# DRS4_GPIO_EXPANDER.net
KiCad netlist of a schematic drawn in Altium Designer
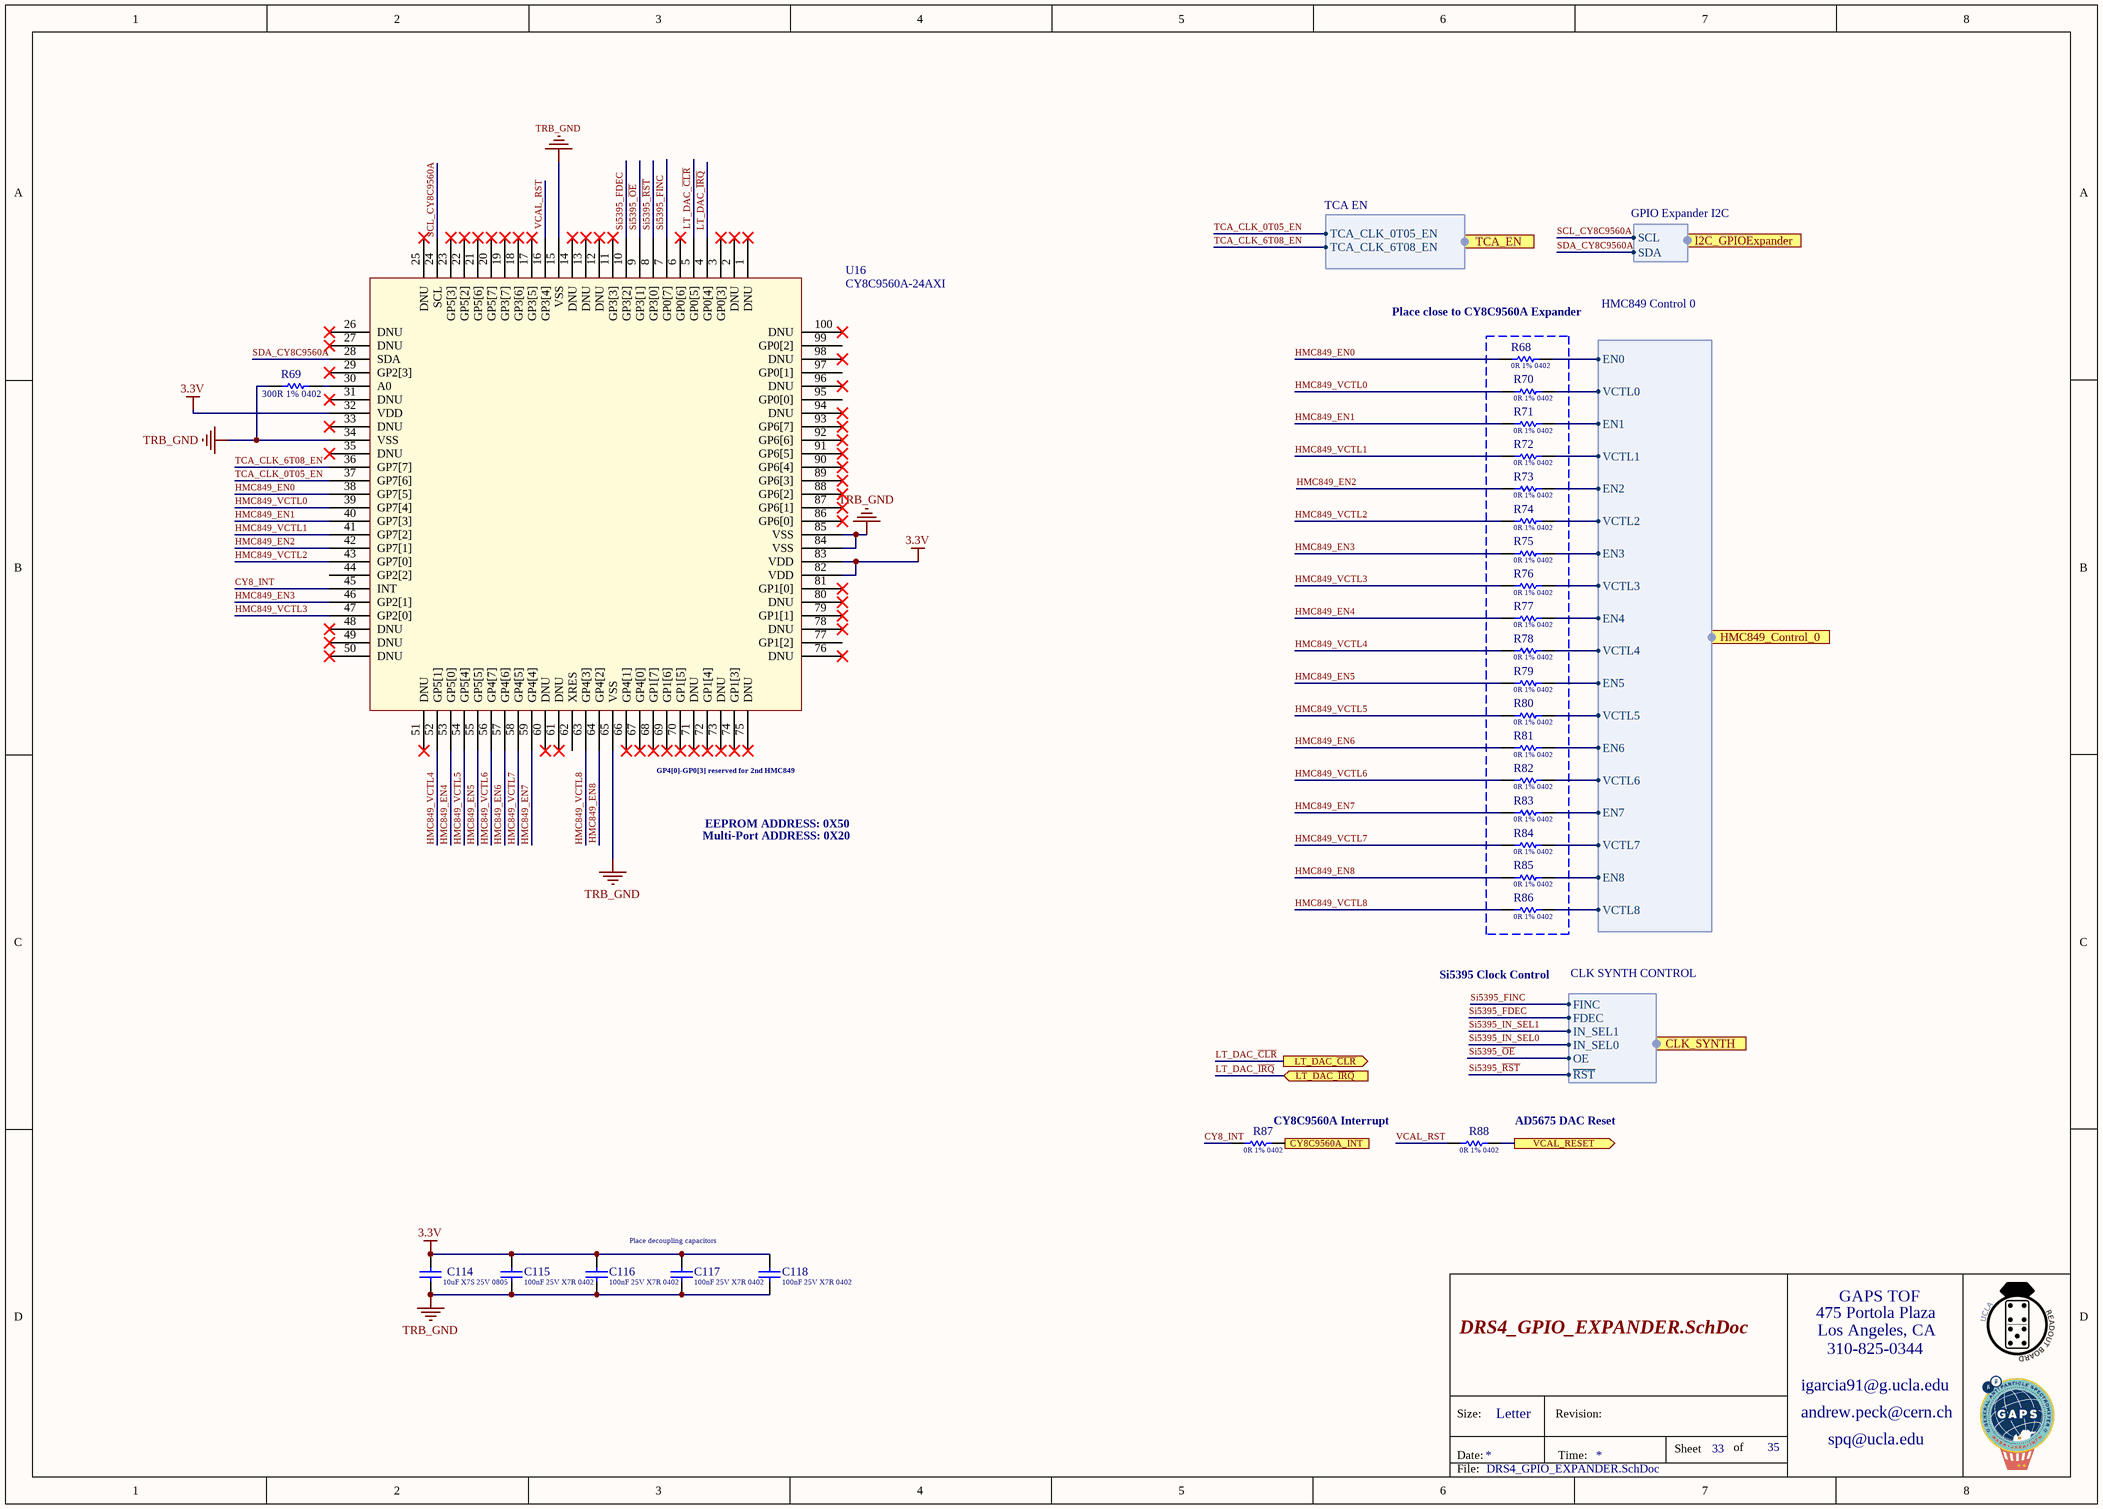
[diagram p0: DRS4_GPIO_EXPANDER.SchDoc]

(export (version "E")
  (design (tool "Eeschema 10.0.6"))
  (components
    (comp (ref "C114")
      (value "Cap_Murata_ GRM21BC71E106ME11L_10uF")
      (footprint "Cap_Murata_ GRM21BC71E106ME11L_10uF")
      (description "CAP CER 10uF 25V X7R 0805")
      (fields (field (name "CAPACITANCE") "10uF X7S 25V 0805"))
      (libsource (lib "Cap_Murata_ GRM21BC71E106ME11L_10uF") (part "Cap_Murata_ GRM21BC71E106ME11L_10uF"))
    )
    (comp (ref "C115")
      (value "Cap_Taiyo_Yuden_TMK105B7104KV-FR_100nF")
      (footprint "Cap_Taiyo_Yuden_TMK105B7104KV-FR_100nF")
      (description "CAP CER 100nF 25V X7R 0402")
      (fields (field (name "CAPACITANCE") "100nF 25V X7R 0402"))
      (libsource (lib "Cap_Taiyo_Yuden_TMK105B7104KV-FR_100nF") (part "Cap_Taiyo_Yuden_TMK105B7104KV-FR_100nF"))
    )
    (comp (ref "C116")
      (value "Cap_Taiyo_Yuden_TMK105B7104KV-FR_100nF")
      (footprint "Cap_Taiyo_Yuden_TMK105B7104KV-FR_100nF")
      (description "CAP CER 100nF 25V X7R 0402")
      (fields (field (name "CAPACITANCE") "100nF 25V X7R 0402"))
      (libsource (lib "Cap_Taiyo_Yuden_TMK105B7104KV-FR_100nF") (part "Cap_Taiyo_Yuden_TMK105B7104KV-FR_100nF"))
    )
    (comp (ref "C117")
      (value "Cap_Taiyo_Yuden_TMK105B7104KV-FR_100nF")
      (footprint "Cap_Taiyo_Yuden_TMK105B7104KV-FR_100nF")
      (description "CAP CER 100nF 25V X7R 0402")
      (fields (field (name "CAPACITANCE") "100nF 25V X7R 0402"))
      (libsource (lib "Cap_Taiyo_Yuden_TMK105B7104KV-FR_100nF") (part "Cap_Taiyo_Yuden_TMK105B7104KV-FR_100nF"))
    )
    (comp (ref "C118")
      (value "Cap_Taiyo_Yuden_TMK105B7104KV-FR_100nF")
      (footprint "Cap_Taiyo_Yuden_TMK105B7104KV-FR_100nF")
      (description "CAP CER 100nF 25V X7R 0402")
      (fields (field (name "CAPACITANCE") "100nF 25V X7R 0402"))
      (libsource (lib "Cap_Taiyo_Yuden_TMK105B7104KV-FR_100nF") (part "Cap_Taiyo_Yuden_TMK105B7104KV-FR_100nF"))
    )
    (comp (ref "R68")
      (value "Res_Vishay_CRCW04020000Z0EDC_0_Ohm")
      (footprint "Res_Vishay_CRCW04020000Z0EDC_0_Ohm")
      (description "0R 0.062W 1% 0402 (1005 Metric)  SMD")
      (fields (field (name "RESISTANCE") "0R 1% 0402"))
      (libsource (lib "Res_Vishay_CRCW04020000Z0EDC_0_Ohm") (part "Res_Vishay_CRCW04020000Z0EDC_0_Ohm"))
    )
    (comp (ref "R69")
      (value "300R 1% 0402")
      (footprint "RESC0402(1005)_L")
      (description "300R 0.063W 1% 0402 (1005 Metric)  SMD")
      (fields (field (name "TOLERANCE") "1 %") (field (name "POWER") "0.063 W"))
      (libsource (lib "Altium Content Vault") (part "RES"))
    )
    (comp (ref "R70")
      (value "Res_Vishay_CRCW04020000Z0EDC_0_Ohm")
      (footprint "Res_Vishay_CRCW04020000Z0EDC_0_Ohm")
      (description "0R 0.062W 1% 0402 (1005 Metric)  SMD")
      (fields (field (name "RESISTANCE") "0R 1% 0402"))
      (libsource (lib "Res_Vishay_CRCW04020000Z0EDC_0_Ohm") (part "Res_Vishay_CRCW04020000Z0EDC_0_Ohm"))
    )
    (comp (ref "R71")
      (value "Res_Vishay_CRCW04020000Z0EDC_0_Ohm")
      (footprint "Res_Vishay_CRCW04020000Z0EDC_0_Ohm")
      (description "0R 0.062W 1% 0402 (1005 Metric)  SMD")
      (fields (field (name "RESISTANCE") "0R 1% 0402"))
      (libsource (lib "Res_Vishay_CRCW04020000Z0EDC_0_Ohm") (part "Res_Vishay_CRCW04020000Z0EDC_0_Ohm"))
    )
    (comp (ref "R72")
      (value "Res_Vishay_CRCW04020000Z0EDC_0_Ohm")
      (footprint "Res_Vishay_CRCW04020000Z0EDC_0_Ohm")
      (description "0R 0.062W 1% 0402 (1005 Metric)  SMD")
      (fields (field (name "RESISTANCE") "0R 1% 0402"))
      (libsource (lib "Res_Vishay_CRCW04020000Z0EDC_0_Ohm") (part "Res_Vishay_CRCW04020000Z0EDC_0_Ohm"))
    )
    (comp (ref "R73")
      (value "Res_Vishay_CRCW04020000Z0EDC_0_Ohm")
      (footprint "Res_Vishay_CRCW04020000Z0EDC_0_Ohm")
      (description "0R 0.062W 1% 0402 (1005 Metric)  SMD")
      (fields (field (name "RESISTANCE") "0R 1% 0402"))
      (libsource (lib "Res_Vishay_CRCW04020000Z0EDC_0_Ohm") (part "Res_Vishay_CRCW04020000Z0EDC_0_Ohm"))
    )
    (comp (ref "R74")
      (value "Res_Vishay_CRCW04020000Z0EDC_0_Ohm")
      (footprint "Res_Vishay_CRCW04020000Z0EDC_0_Ohm")
      (description "0R 0.062W 1% 0402 (1005 Metric)  SMD")
      (fields (field (name "RESISTANCE") "0R 1% 0402"))
      (libsource (lib "Res_Vishay_CRCW04020000Z0EDC_0_Ohm") (part "Res_Vishay_CRCW04020000Z0EDC_0_Ohm"))
    )
    (comp (ref "R75")
      (value "Res_Vishay_CRCW04020000Z0EDC_0_Ohm")
      (footprint "Res_Vishay_CRCW04020000Z0EDC_0_Ohm")
      (description "0R 0.062W 1% 0402 (1005 Metric)  SMD")
      (fields (field (name "RESISTANCE") "0R 1% 0402"))
      (libsource (lib "Res_Vishay_CRCW04020000Z0EDC_0_Ohm") (part "Res_Vishay_CRCW04020000Z0EDC_0_Ohm"))
    )
    (comp (ref "R76")
      (value "Res_Vishay_CRCW04020000Z0EDC_0_Ohm")
      (footprint "Res_Vishay_CRCW04020000Z0EDC_0_Ohm")
      (description "0R 0.062W 1% 0402 (1005 Metric)  SMD")
      (fields (field (name "RESISTANCE") "0R 1% 0402"))
      (libsource (lib "Res_Vishay_CRCW04020000Z0EDC_0_Ohm") (part "Res_Vishay_CRCW04020000Z0EDC_0_Ohm"))
    )
    (comp (ref "R77")
      (value "Res_Vishay_CRCW04020000Z0EDC_0_Ohm")
      (footprint "Res_Vishay_CRCW04020000Z0EDC_0_Ohm")
      (description "0R 0.062W 1% 0402 (1005 Metric)  SMD")
      (fields (field (name "RESISTANCE") "0R 1% 0402"))
      (libsource (lib "Res_Vishay_CRCW04020000Z0EDC_0_Ohm") (part "Res_Vishay_CRCW04020000Z0EDC_0_Ohm"))
    )
    (comp (ref "R78")
      (value "Res_Vishay_CRCW04020000Z0EDC_0_Ohm")
      (footprint "Res_Vishay_CRCW04020000Z0EDC_0_Ohm")
      (description "0R 0.062W 1% 0402 (1005 Metric)  SMD")
      (fields (field (name "RESISTANCE") "0R 1% 0402"))
      (libsource (lib "Res_Vishay_CRCW04020000Z0EDC_0_Ohm") (part "Res_Vishay_CRCW04020000Z0EDC_0_Ohm"))
    )
    (comp (ref "R79")
      (value "Res_Vishay_CRCW04020000Z0EDC_0_Ohm")
      (footprint "Res_Vishay_CRCW04020000Z0EDC_0_Ohm")
      (description "0R 0.062W 1% 0402 (1005 Metric)  SMD")
      (fields (field (name "RESISTANCE") "0R 1% 0402"))
      (libsource (lib "Res_Vishay_CRCW04020000Z0EDC_0_Ohm") (part "Res_Vishay_CRCW04020000Z0EDC_0_Ohm"))
    )
    (comp (ref "R80")
      (value "Res_Vishay_CRCW04020000Z0EDC_0_Ohm")
      (footprint "Res_Vishay_CRCW04020000Z0EDC_0_Ohm")
      (description "0R 0.062W 1% 0402 (1005 Metric)  SMD")
      (fields (field (name "RESISTANCE") "0R 1% 0402"))
      (libsource (lib "Res_Vishay_CRCW04020000Z0EDC_0_Ohm") (part "Res_Vishay_CRCW04020000Z0EDC_0_Ohm"))
    )
    (comp (ref "R81")
      (value "Res_Vishay_CRCW04020000Z0EDC_0_Ohm")
      (footprint "Res_Vishay_CRCW04020000Z0EDC_0_Ohm")
      (description "0R 0.062W 1% 0402 (1005 Metric)  SMD")
      (fields (field (name "RESISTANCE") "0R 1% 0402"))
      (libsource (lib "Res_Vishay_CRCW04020000Z0EDC_0_Ohm") (part "Res_Vishay_CRCW04020000Z0EDC_0_Ohm"))
    )
    (comp (ref "R82")
      (value "Res_Vishay_CRCW04020000Z0EDC_0_Ohm")
      (footprint "Res_Vishay_CRCW04020000Z0EDC_0_Ohm")
      (description "0R 0.062W 1% 0402 (1005 Metric)  SMD")
      (fields (field (name "RESISTANCE") "0R 1% 0402"))
      (libsource (lib "Res_Vishay_CRCW04020000Z0EDC_0_Ohm") (part "Res_Vishay_CRCW04020000Z0EDC_0_Ohm"))
    )
    (comp (ref "R83")
      (value "Res_Vishay_CRCW04020000Z0EDC_0_Ohm")
      (footprint "Res_Vishay_CRCW04020000Z0EDC_0_Ohm")
      (description "0R 0.062W 1% 0402 (1005 Metric)  SMD")
      (fields (field (name "RESISTANCE") "0R 1% 0402"))
      (libsource (lib "Res_Vishay_CRCW04020000Z0EDC_0_Ohm") (part "Res_Vishay_CRCW04020000Z0EDC_0_Ohm"))
    )
    (comp (ref "R84")
      (value "Res_Vishay_CRCW04020000Z0EDC_0_Ohm")
      (footprint "Res_Vishay_CRCW04020000Z0EDC_0_Ohm")
      (description "0R 0.062W 1% 0402 (1005 Metric)  SMD")
      (fields (field (name "RESISTANCE") "0R 1% 0402"))
      (libsource (lib "Res_Vishay_CRCW04020000Z0EDC_0_Ohm") (part "Res_Vishay_CRCW04020000Z0EDC_0_Ohm"))
    )
    (comp (ref "R85")
      (value "Res_Vishay_CRCW04020000Z0EDC_0_Ohm")
      (footprint "Res_Vishay_CRCW04020000Z0EDC_0_Ohm")
      (description "0R 0.062W 1% 0402 (1005 Metric)  SMD")
      (fields (field (name "RESISTANCE") "0R 1% 0402"))
      (libsource (lib "Res_Vishay_CRCW04020000Z0EDC_0_Ohm") (part "Res_Vishay_CRCW04020000Z0EDC_0_Ohm"))
    )
    (comp (ref "R86")
      (value "Res_Vishay_CRCW04020000Z0EDC_0_Ohm")
      (footprint "Res_Vishay_CRCW04020000Z0EDC_0_Ohm")
      (description "0R 0.062W 1% 0402 (1005 Metric)  SMD")
      (fields (field (name "RESISTANCE") "0R 1% 0402"))
      (libsource (lib "Res_Vishay_CRCW04020000Z0EDC_0_Ohm") (part "Res_Vishay_CRCW04020000Z0EDC_0_Ohm"))
    )
    (comp (ref "R87")
      (value "Res_Vishay_CRCW04020000Z0EDC_0_Ohm")
      (footprint "Res_Vishay_CRCW04020000Z0EDC_0_Ohm")
      (description "0R 0.062W 1% 0402 (1005 Metric)  SMD")
      (fields (field (name "RESISTANCE") "0R 1% 0402"))
      (libsource (lib "Res_Vishay_CRCW04020000Z0EDC_0_Ohm") (part "Res_Vishay_CRCW04020000Z0EDC_0_Ohm"))
    )
    (comp (ref "R88")
      (value "Res_Vishay_CRCW04020000Z0EDC_0_Ohm")
      (footprint "Res_Vishay_CRCW04020000Z0EDC_0_Ohm")
      (description "0R 0.062W 1% 0402 (1005 Metric)  SMD")
      (fields (field (name "RESISTANCE") "0R 1% 0402"))
      (libsource (lib "Res_Vishay_CRCW04020000Z0EDC_0_Ohm") (part "Res_Vishay_CRCW04020000Z0EDC_0_Ohm"))
    )
    (comp (ref "U16")
      (value "IC_Cypress_Semiconductor_CY8C9560A-24AXI")
      (footprint "IC_Cypress_Semiconductor_CY8C9560A-24AXI")
      (description "Interface - I/O Expanders 60BIT IO EXPANDER W/EEPROM")
      (fields (field (name "SERIES") "CY8C9560A-24AXI"))
      (libsource (lib "IC_Cypress_Semiconductor_CY8C9560A-24AXI") (part "IC_Cypress_Semiconductor_CY8C9560A-24AXI"))
    )
  )
  (nets
    (net (code "12") (name "/CY8C9560A_INT") (class "Default")
      (node (ref "R87") (pin "1") (pinfunction "1_1") (pintype "passive"))
    )
    (net (code "13") (name "/CY8_INT") (class "Default")
      (node (ref "R87") (pin "2") (pinfunction "2_2") (pintype "passive"))
      (node (ref "U16") (pin "45") (pinfunction "INT_45") (pintype "passive"))
    )
    (net (code "14") (name "/EN0") (class "Default")
      (node (ref "R68") (pin "2") (pinfunction "2_2") (pintype "passive"))
    )
    (net (code "15") (name "/EN1") (class "Default")
      (node (ref "R71") (pin "2") (pinfunction "2_2") (pintype "passive"))
    )
    (net (code "16") (name "/EN2") (class "Default")
      (node (ref "R73") (pin "2") (pinfunction "2_2") (pintype "passive"))
    )
    (net (code "17") (name "/EN3") (class "Default")
      (node (ref "R75") (pin "2") (pinfunction "2_2") (pintype "passive"))
    )
    (net (code "18") (name "/EN4") (class "Default")
      (node (ref "R77") (pin "2") (pinfunction "2_2") (pintype "passive"))
    )
    (net (code "19") (name "/EN5") (class "Default")
      (node (ref "R79") (pin "2") (pinfunction "2_2") (pintype "passive"))
    )
    (net (code "20") (name "/EN6") (class "Default")
      (node (ref "R81") (pin "2") (pinfunction "2_2") (pintype "passive"))
    )
    (net (code "21") (name "/EN7") (class "Default")
      (node (ref "R83") (pin "2") (pinfunction "2_2") (pintype "passive"))
    )
    (net (code "22") (name "/EN8") (class "Default")
      (node (ref "R85") (pin "2") (pinfunction "2_2") (pintype "passive"))
    )
    (net (code "23") (name "/HMC849_EN0") (class "Default")
      (node (ref "R68") (pin "1") (pinfunction "1_1") (pintype "passive"))
      (node (ref "U16") (pin "38") (pinfunction "GP7[5]_38") (pintype "passive"))
    )
    (net (code "24") (name "/HMC849_EN1") (class "Default")
      (node (ref "R71") (pin "1") (pinfunction "1_1") (pintype "passive"))
      (node (ref "U16") (pin "40") (pinfunction "GP7[3]_40") (pintype "passive"))
    )
    (net (code "25") (name "/HMC849_EN2") (class "Default")
      (node (ref "R73") (pin "1") (pinfunction "1_1") (pintype "passive"))
      (node (ref "U16") (pin "42") (pinfunction "GP7[1]_42") (pintype "passive"))
    )
    (net (code "26") (name "/HMC849_EN3") (class "Default")
      (node (ref "R75") (pin "1") (pinfunction "1_1") (pintype "passive"))
      (node (ref "U16") (pin "46") (pinfunction "GP2[1]_46") (pintype "passive"))
    )
    (net (code "27") (name "/HMC849_EN4") (class "Default")
      (node (ref "R77") (pin "1") (pinfunction "1_1") (pintype "passive"))
      (node (ref "U16") (pin "53") (pinfunction "GP5[0]_53") (pintype "passive"))
    )
    (net (code "28") (name "/HMC849_EN5") (class "Default")
      (node (ref "R79") (pin "1") (pinfunction "1_1") (pintype "passive"))
      (node (ref "U16") (pin "55") (pinfunction "GP5[5]_55") (pintype "passive"))
    )
    (net (code "29") (name "/HMC849_EN6") (class "Default")
      (node (ref "R81") (pin "1") (pinfunction "1_1") (pintype "passive"))
      (node (ref "U16") (pin "57") (pinfunction "GP4[6]_57") (pintype "passive"))
    )
    (net (code "30") (name "/HMC849_EN7") (class "Default")
      (node (ref "R83") (pin "1") (pinfunction "1_1") (pintype "passive"))
      (node (ref "U16") (pin "59") (pinfunction "GP4[4]_59") (pintype "passive"))
    )
    (net (code "31") (name "/HMC849_EN8") (class "Default")
      (node (ref "R85") (pin "1") (pinfunction "1_1") (pintype "passive"))
      (node (ref "U16") (pin "64") (pinfunction "GP4[2]_64") (pintype "passive"))
    )
    (net (code "32") (name "/HMC849_VCTL0") (class "Default")
      (node (ref "R70") (pin "1") (pinfunction "1_1") (pintype "passive"))
      (node (ref "U16") (pin "39") (pinfunction "GP7[4]_39") (pintype "passive"))
    )
    (net (code "33") (name "/HMC849_VCTL1") (class "Default")
      (node (ref "R72") (pin "1") (pinfunction "1_1") (pintype "passive"))
      (node (ref "U16") (pin "41") (pinfunction "GP7[2]_41") (pintype "passive"))
    )
    (net (code "34") (name "/HMC849_VCTL2") (class "Default")
      (node (ref "R74") (pin "1") (pinfunction "1_1") (pintype "passive"))
      (node (ref "U16") (pin "43") (pinfunction "GP7[0]_43") (pintype "passive"))
    )
    (net (code "35") (name "/HMC849_VCTL3") (class "Default")
      (node (ref "R76") (pin "1") (pinfunction "1_1") (pintype "passive"))
      (node (ref "U16") (pin "47") (pinfunction "GP2[0]_47") (pintype "passive"))
    )
    (net (code "36") (name "/HMC849_VCTL4") (class "Default")
      (node (ref "R78") (pin "1") (pinfunction "1_1") (pintype "passive"))
      (node (ref "U16") (pin "52") (pinfunction "GP5[1]_52") (pintype "passive"))
    )
    (net (code "37") (name "/HMC849_VCTL5") (class "Default")
      (node (ref "R80") (pin "1") (pinfunction "1_1") (pintype "passive"))
      (node (ref "U16") (pin "54") (pinfunction "GP5[4]_54") (pintype "passive"))
    )
    (net (code "38") (name "/HMC849_VCTL6") (class "Default")
      (node (ref "R82") (pin "1") (pinfunction "1_1") (pintype "passive"))
      (node (ref "U16") (pin "56") (pinfunction "GP4[7]_56") (pintype "passive"))
    )
    (net (code "39") (name "/HMC849_VCTL7") (class "Default")
      (node (ref "R84") (pin "1") (pinfunction "1_1") (pintype "passive"))
      (node (ref "U16") (pin "58") (pinfunction "GP4[5]_58") (pintype "passive"))
    )
    (net (code "40") (name "/HMC849_VCTL8") (class "Default")
      (node (ref "R86") (pin "1") (pinfunction "1_1") (pintype "passive"))
      (node (ref "U16") (pin "63") (pinfunction "GP4[3]_63") (pintype "passive"))
    )
    (net (code "41") (name "/LT_DAC_~{CLR}") (class "Default")
      (node (ref "U16") (pin "5") (pinfunction "GP0[5]_5") (pintype "passive"))
    )
    (net (code "42") (name "/LT_DAC_~{IRQ}") (class "Default")
      (node (ref "U16") (pin "4") (pinfunction "GP0[4]_4") (pintype "passive"))
    )
    (net (code "43") (name "/SCL_CY8C9560A") (class "Default")
      (node (ref "U16") (pin "24") (pinfunction "SCL_24") (pintype "passive"))
    )
    (net (code "44") (name "/SDA_CY8C9560A") (class "Default")
      (node (ref "U16") (pin "28") (pinfunction "SDA_28") (pintype "passive"))
    )
    (net (code "45") (name "/Si5395_FDEC") (class "Default")
      (node (ref "U16") (pin "10") (pinfunction "GP3[2]_10") (pintype "passive"))
    )
    (net (code "46") (name "/Si5395_FINC") (class "Default")
      (node (ref "U16") (pin "7") (pinfunction "GP0[7]_7") (pintype "passive"))
    )
    (net (code "49") (name "/Si5395_~{OE}") (class "Default")
      (node (ref "U16") (pin "9") (pinfunction "GP3[1]_9") (pintype "passive"))
    )
    (net (code "50") (name "/Si5395_~{RST}") (class "Default")
      (node (ref "U16") (pin "8") (pinfunction "GP3[0]_8") (pintype "passive"))
    )
    (net (code "51") (name "/TCA_CLK_0T05_EN") (class "Default")
      (node (ref "U16") (pin "37") (pinfunction "GP7[6]_37") (pintype "passive"))
    )
    (net (code "52") (name "/TCA_CLK_6T08_EN") (class "Default")
      (node (ref "U16") (pin "36") (pinfunction "GP7[7]_36") (pintype "passive"))
    )
    (net (code "53") (name "/VCAL_RESET") (class "Default")
      (node (ref "R88") (pin "1") (pinfunction "1_1") (pintype "passive"))
    )
    (net (code "54") (name "/VCAL_RST") (class "Default")
      (node (ref "R88") (pin "2") (pinfunction "2_2") (pintype "passive"))
      (node (ref "U16") (pin "16") (pinfunction "GP3[4]_16") (pintype "passive"))
    )
    (net (code "55") (name "/VCTL0") (class "Default")
      (node (ref "R70") (pin "2") (pinfunction "2_2") (pintype "passive"))
    )
    (net (code "56") (name "/VCTL1") (class "Default")
      (node (ref "R72") (pin "2") (pinfunction "2_2") (pintype "passive"))
    )
    (net (code "57") (name "/VCTL2") (class "Default")
      (node (ref "R74") (pin "2") (pinfunction "2_2") (pintype "passive"))
    )
    (net (code "58") (name "/VCTL3") (class "Default")
      (node (ref "R76") (pin "2") (pinfunction "2_2") (pintype "passive"))
    )
    (net (code "59") (name "/VCTL4") (class "Default")
      (node (ref "R78") (pin "2") (pinfunction "2_2") (pintype "passive"))
    )
    (net (code "60") (name "/VCTL5") (class "Default")
      (node (ref "R80") (pin "2") (pinfunction "2_2") (pintype "passive"))
    )
    (net (code "61") (name "/VCTL6") (class "Default")
      (node (ref "R82") (pin "2") (pinfunction "2_2") (pintype "passive"))
    )
    (net (code "62") (name "/VCTL7") (class "Default")
      (node (ref "R84") (pin "2") (pinfunction "2_2") (pintype "passive"))
    )
    (net (code "63") (name "/VCTL8") (class "Default")
      (node (ref "R86") (pin "2") (pinfunction "2_2") (pintype "passive"))
    )
    (net (code "68") (name "3.3V") (class "Default")
      (node (ref "C114") (pin "1") (pinfunction "1_1") (pintype "passive"))
      (node (ref "C115") (pin "2") (pinfunction "2_2") (pintype "passive"))
      (node (ref "C116") (pin "2") (pinfunction "2_2") (pintype "passive"))
      (node (ref "C117") (pin "2") (pinfunction "2_2") (pintype "passive"))
      (node (ref "C118") (pin "2") (pinfunction "2_2") (pintype "passive"))
      (node (ref "U16") (pin "32") (pinfunction "VDD_32") (pintype "passive"))
      (node (ref "U16") (pin "82") (pinfunction "VDD_82") (pintype "passive"))
      (node (ref "U16") (pin "83") (pinfunction "VDD_83") (pintype "passive"))
    )
    (net (code "69") (name "Net-(U16-A0)") (class "Default")
      (node (ref "R69") (pin "1") (pinfunction "1_1") (pintype "passive"))
      (node (ref "U16") (pin "30") (pinfunction "A0_30") (pintype "passive"))
    )
    (net (code "70") (name "TRB_GND") (class "Default")
      (node (ref "C114") (pin "2") (pinfunction "2_2") (pintype "passive"))
      (node (ref "C115") (pin "1") (pinfunction "1_1") (pintype "passive"))
      (node (ref "C116") (pin "1") (pinfunction "1_1") (pintype "passive"))
      (node (ref "C117") (pin "1") (pinfunction "1_1") (pintype "passive"))
      (node (ref "C118") (pin "1") (pinfunction "1_1") (pintype "passive"))
      (node (ref "R69") (pin "2") (pinfunction "2_2") (pintype "passive"))
      (node (ref "U16") (pin "15") (pinfunction "VSS_15") (pintype "passive"))
      (node (ref "U16") (pin "34") (pinfunction "VSS_34") (pintype "passive"))
      (node (ref "U16") (pin "65") (pinfunction "VSS_65") (pintype "passive"))
      (node (ref "U16") (pin "84") (pinfunction "VSS_84") (pintype "passive"))
      (node (ref "U16") (pin "85") (pinfunction "VSS_85") (pintype "passive"))
    )
    (net (code "71") (name "unconnected-(U16-DNU-Pad1)") (class "Default")
      (node (ref "U16") (pin "1") (pinfunction "DNU_1") (pintype "passive+no_connect"))
    )
    (net (code "72") (name "unconnected-(U16-DNU-Pad2)") (class "Default")
      (node (ref "U16") (pin "2") (pinfunction "DNU_2") (pintype "passive+no_connect"))
    )
    (net (code "73") (name "unconnected-(U16-DNU-Pad12)") (class "Default")
      (node (ref "U16") (pin "12") (pinfunction "DNU_12") (pintype "passive+no_connect"))
    )
    (net (code "74") (name "unconnected-(U16-DNU-Pad13)") (class "Default")
      (node (ref "U16") (pin "13") (pinfunction "DNU_13") (pintype "passive+no_connect"))
    )
    (net (code "75") (name "unconnected-(U16-DNU-Pad14)") (class "Default")
      (node (ref "U16") (pin "14") (pinfunction "DNU_14") (pintype "passive+no_connect"))
    )
    (net (code "76") (name "unconnected-(U16-DNU-Pad25)") (class "Default")
      (node (ref "U16") (pin "25") (pinfunction "DNU_25") (pintype "passive+no_connect"))
    )
    (net (code "77") (name "unconnected-(U16-DNU-Pad26)") (class "Default")
      (node (ref "U16") (pin "26") (pinfunction "DNU_26") (pintype "passive+no_connect"))
    )
    (net (code "78") (name "unconnected-(U16-DNU-Pad27)") (class "Default")
      (node (ref "U16") (pin "27") (pinfunction "DNU_27") (pintype "passive+no_connect"))
    )
    (net (code "79") (name "unconnected-(U16-DNU-Pad31)") (class "Default")
      (node (ref "U16") (pin "31") (pinfunction "DNU_31") (pintype "passive+no_connect"))
    )
    (net (code "80") (name "unconnected-(U16-DNU-Pad33)") (class "Default")
      (node (ref "U16") (pin "33") (pinfunction "DNU_33") (pintype "passive+no_connect"))
    )
    (net (code "81") (name "unconnected-(U16-DNU-Pad35)") (class "Default")
      (node (ref "U16") (pin "35") (pinfunction "DNU_35") (pintype "passive+no_connect"))
    )
    (net (code "82") (name "unconnected-(U16-DNU-Pad48)") (class "Default")
      (node (ref "U16") (pin "48") (pinfunction "DNU_48") (pintype "passive+no_connect"))
    )
    (net (code "83") (name "unconnected-(U16-DNU-Pad49)") (class "Default")
      (node (ref "U16") (pin "49") (pinfunction "DNU_49") (pintype "passive+no_connect"))
    )
    (net (code "84") (name "unconnected-(U16-DNU-Pad50)") (class "Default")
      (node (ref "U16") (pin "50") (pinfunction "DNU_50") (pintype "passive+no_connect"))
    )
    (net (code "85") (name "unconnected-(U16-DNU-Pad51)") (class "Default")
      (node (ref "U16") (pin "51") (pinfunction "DNU_51") (pintype "passive+no_connect"))
    )
    (net (code "86") (name "unconnected-(U16-DNU-Pad60)") (class "Default")
      (node (ref "U16") (pin "60") (pinfunction "DNU_60") (pintype "passive+no_connect"))
    )
    (net (code "87") (name "unconnected-(U16-DNU-Pad61)") (class "Default")
      (node (ref "U16") (pin "61") (pinfunction "DNU_61") (pintype "passive+no_connect"))
    )
    (net (code "88") (name "unconnected-(U16-DNU-Pad71)") (class "Default")
      (node (ref "U16") (pin "71") (pinfunction "DNU_71") (pintype "passive+no_connect"))
    )
    (net (code "89") (name "unconnected-(U16-DNU-Pad73)") (class "Default")
      (node (ref "U16") (pin "73") (pinfunction "DNU_73") (pintype "passive+no_connect"))
    )
    (net (code "90") (name "unconnected-(U16-DNU-Pad75)") (class "Default")
      (node (ref "U16") (pin "75") (pinfunction "DNU_75") (pintype "passive+no_connect"))
    )
    (net (code "91") (name "unconnected-(U16-DNU-Pad76)") (class "Default")
      (node (ref "U16") (pin "76") (pinfunction "DNU_76") (pintype "passive+no_connect"))
    )
    (net (code "92") (name "unconnected-(U16-DNU-Pad78)") (class "Default")
      (node (ref "U16") (pin "78") (pinfunction "DNU_78") (pintype "passive+no_connect"))
    )
    (net (code "93") (name "unconnected-(U16-DNU-Pad80)") (class "Default")
      (node (ref "U16") (pin "80") (pinfunction "DNU_80") (pintype "passive+no_connect"))
    )
    (net (code "94") (name "unconnected-(U16-DNU-Pad94)") (class "Default")
      (node (ref "U16") (pin "94") (pinfunction "DNU_94") (pintype "passive+no_connect"))
    )
    (net (code "95") (name "unconnected-(U16-DNU-Pad96)") (class "Default")
      (node (ref "U16") (pin "96") (pinfunction "DNU_96") (pintype "passive+no_connect"))
    )
    (net (code "96") (name "unconnected-(U16-DNU-Pad98)") (class "Default")
      (node (ref "U16") (pin "98") (pinfunction "DNU_98") (pintype "passive+no_connect"))
    )
    (net (code "97") (name "unconnected-(U16-DNU-Pad100)") (class "Default")
      (node (ref "U16") (pin "100") (pinfunction "DNU_100") (pintype "passive+no_connect"))
    )
    (net (code "98") (name "unconnected-(U16-GP0[0]-Pad95)") (class "Default")
      (node (ref "U16") (pin "95") (pinfunction "GP0[0]_95") (pintype "passive"))
    )
    (net (code "99") (name "unconnected-(U16-GP0[1]-Pad97)") (class "Default")
      (node (ref "U16") (pin "97") (pinfunction "GP0[1]_97") (pintype "passive"))
    )
    (net (code "100") (name "unconnected-(U16-GP0[2]-Pad99)") (class "Default")
      (node (ref "U16") (pin "99") (pinfunction "GP0[2]_99") (pintype "passive"))
    )
    (net (code "101") (name "unconnected-(U16-GP0[3]-Pad3)") (class "Default")
      (node (ref "U16") (pin "3") (pinfunction "GP0[3]_3") (pintype "passive+no_connect"))
    )
    (net (code "102") (name "unconnected-(U16-GP0[6]-Pad6)") (class "Default")
      (node (ref "U16") (pin "6") (pinfunction "GP0[6]_6") (pintype "passive+no_connect"))
    )
    (net (code "103") (name "unconnected-(U16-GP1[0]-Pad81)") (class "Default")
      (node (ref "U16") (pin "81") (pinfunction "GP1[0]_81") (pintype "passive+no_connect"))
    )
    (net (code "104") (name "unconnected-(U16-GP1[1]-Pad79)") (class "Default")
      (node (ref "U16") (pin "79") (pinfunction "GP1[1]_79") (pintype "passive+no_connect"))
    )
    (net (code "105") (name "unconnected-(U16-GP1[2]-Pad77)") (class "Default")
      (node (ref "U16") (pin "77") (pinfunction "GP1[2]_77") (pintype "passive"))
    )
    (net (code "106") (name "unconnected-(U16-GP1[3]-Pad74)") (class "Default")
      (node (ref "U16") (pin "74") (pinfunction "GP1[3]_74") (pintype "passive+no_connect"))
    )
    (net (code "107") (name "unconnected-(U16-GP1[4]-Pad72)") (class "Default")
      (node (ref "U16") (pin "72") (pinfunction "GP1[4]_72") (pintype "passive+no_connect"))
    )
    (net (code "108") (name "unconnected-(U16-GP1[5]-Pad70)") (class "Default")
      (node (ref "U16") (pin "70") (pinfunction "GP1[5]_70") (pintype "passive+no_connect"))
    )
    (net (code "109") (name "unconnected-(U16-GP1[6]-Pad69)") (class "Default")
      (node (ref "U16") (pin "69") (pinfunction "GP1[6]_69") (pintype "passive+no_connect"))
    )
    (net (code "110") (name "unconnected-(U16-GP1[7]-Pad68)") (class "Default")
      (node (ref "U16") (pin "68") (pinfunction "GP1[7]_68") (pintype "passive+no_connect"))
    )
    (net (code "111") (name "unconnected-(U16-GP2[2]-Pad44)") (class "Default")
      (node (ref "U16") (pin "44") (pinfunction "GP2[2]_44") (pintype "passive"))
    )
    (net (code "112") (name "unconnected-(U16-GP2[3]-Pad29)") (class "Default")
      (node (ref "U16") (pin "29") (pinfunction "GP2[3]_29") (pintype "passive+no_connect"))
    )
    (net (code "113") (name "unconnected-(U16-GP3[3]-Pad11)") (class "Default")
      (node (ref "U16") (pin "11") (pinfunction "GP3[3]_11") (pintype "passive+no_connect"))
    )
    (net (code "114") (name "unconnected-(U16-GP3[5]-Pad17)") (class "Default")
      (node (ref "U16") (pin "17") (pinfunction "GP3[5]_17") (pintype "passive+no_connect"))
    )
    (net (code "115") (name "unconnected-(U16-GP3[6]-Pad18)") (class "Default")
      (node (ref "U16") (pin "18") (pinfunction "GP3[6]_18") (pintype "passive+no_connect"))
    )
    (net (code "116") (name "unconnected-(U16-GP3[7]-Pad19)") (class "Default")
      (node (ref "U16") (pin "19") (pinfunction "GP3[7]_19") (pintype "passive+no_connect"))
    )
    (net (code "117") (name "unconnected-(U16-GP4[0]-Pad67)") (class "Default")
      (node (ref "U16") (pin "67") (pinfunction "GP4[0]_67") (pintype "passive+no_connect"))
    )
    (net (code "118") (name "unconnected-(U16-GP4[1]-Pad66)") (class "Default")
      (node (ref "U16") (pin "66") (pinfunction "GP4[1]_66") (pintype "passive+no_connect"))
    )
    (net (code "119") (name "unconnected-(U16-GP5[2]-Pad22)") (class "Default")
      (node (ref "U16") (pin "22") (pinfunction "GP5[2]_22") (pintype "passive+no_connect"))
    )
    (net (code "120") (name "unconnected-(U16-GP5[3]-Pad23)") (class "Default")
      (node (ref "U16") (pin "23") (pinfunction "GP5[3]_23") (pintype "passive+no_connect"))
    )
    (net (code "121") (name "unconnected-(U16-GP5[6]-Pad21)") (class "Default")
      (node (ref "U16") (pin "21") (pinfunction "GP5[6]_21") (pintype "passive+no_connect"))
    )
    (net (code "122") (name "unconnected-(U16-GP5[7]-Pad20)") (class "Default")
      (node (ref "U16") (pin "20") (pinfunction "GP5[7]_20") (pintype "passive+no_connect"))
    )
    (net (code "123") (name "unconnected-(U16-GP6[0]-Pad86)") (class "Default")
      (node (ref "U16") (pin "86") (pinfunction "GP6[0]_86") (pintype "passive+no_connect"))
    )
    (net (code "124") (name "unconnected-(U16-GP6[1]-Pad87)") (class "Default")
      (node (ref "U16") (pin "87") (pinfunction "GP6[1]_87") (pintype "passive+no_connect"))
    )
    (net (code "125") (name "unconnected-(U16-GP6[2]-Pad88)") (class "Default")
      (node (ref "U16") (pin "88") (pinfunction "GP6[2]_88") (pintype "passive+no_connect"))
    )
    (net (code "126") (name "unconnected-(U16-GP6[3]-Pad89)") (class "Default")
      (node (ref "U16") (pin "89") (pinfunction "GP6[3]_89") (pintype "passive+no_connect"))
    )
    (net (code "127") (name "unconnected-(U16-GP6[4]-Pad90)") (class "Default")
      (node (ref "U16") (pin "90") (pinfunction "GP6[4]_90") (pintype "passive+no_connect"))
    )
    (net (code "128") (name "unconnected-(U16-GP6[5]-Pad91)") (class "Default")
      (node (ref "U16") (pin "91") (pinfunction "GP6[5]_91") (pintype "passive+no_connect"))
    )
    (net (code "129") (name "unconnected-(U16-GP6[6]-Pad92)") (class "Default")
      (node (ref "U16") (pin "92") (pinfunction "GP6[6]_92") (pintype "passive+no_connect"))
    )
    (net (code "130") (name "unconnected-(U16-GP6[7]-Pad93)") (class "Default")
      (node (ref "U16") (pin "93") (pinfunction "GP6[7]_93") (pintype "passive+no_connect"))
    )
    (net (code "131") (name "unconnected-(U16-XRES-Pad62)") (class "Default")
      (node (ref "U16") (pin "62") (pinfunction "XRES_62") (pintype "passive"))
    )
  )
)
